# USBtoUART.net
KiCad netlist of a schematic drawn in Altium Designer
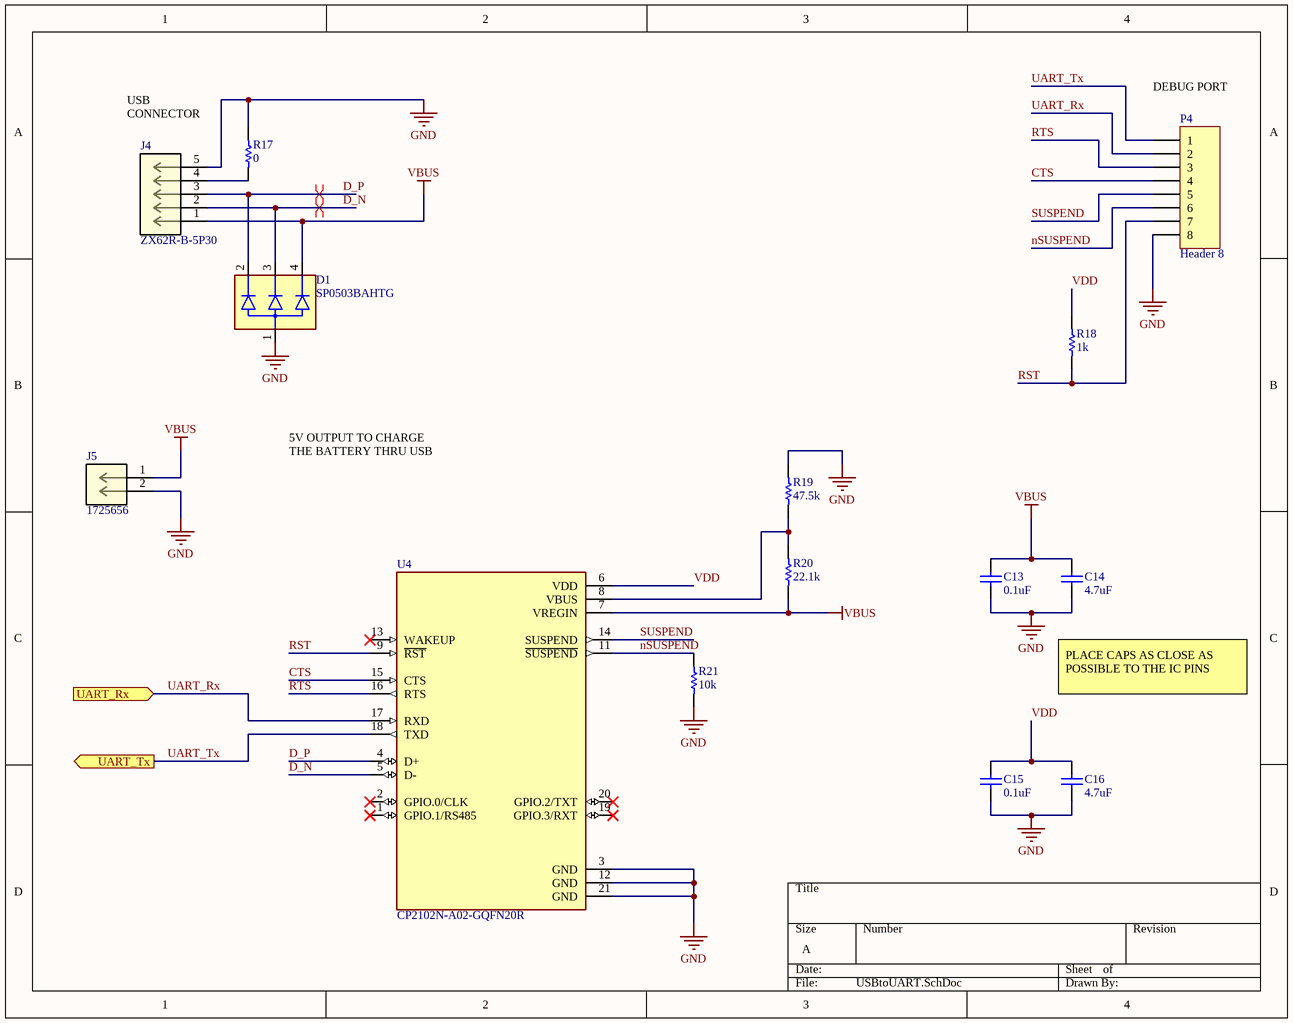
[diagram p0: USBtoUART.SchDoc]

(export (version "E")
  (design (tool "Eeschema 10.0.6"))
  (components
    (comp (ref "C13")
      (value "0.1uF")
      (footprint "0402cap")
      (description "0402 Ceramic Chip Capacitor - Standard")
      (fields (field (name "Comment") "C0402"))
      (libsource (lib "Standard Components") (part "C0402"))
    )
    (comp (ref "C14")
      (value "4.7uF")
      (footprint "0805CAP")
      (description "0805 Ceramic Chip Capacitor - Standard")
      (fields (field (name "Comment") "C0805"))
      (libsource (lib "Standard Components") (part "C0805"))
    )
    (comp (ref "C15")
      (value "0.1uF")
      (footprint "0402cap")
      (description "0402 Ceramic Chip Capacitor - Standard")
      (fields (field (name "Comment") "C0402"))
      (libsource (lib "Standard Components") (part "C0402"))
    )
    (comp (ref "C16")
      (value "4.7uF")
      (footprint "0805CAP")
      (description "0805 Ceramic Chip Capacitor - Standard")
      (fields (field (name "Comment") "C0805"))
      (libsource (lib "Standard Components") (part "C0805"))
    )
    (comp (ref "D1")
      (value "SP0503BAHTG")
      (footprint "SOT143")
      (fields (field (name "MF") "{'manufacturer': u'Littelfuse Inc.'}"))
      (libsource (lib "SP0503BAHTG_Zenner diodes") (part "SP0503BAHTG"))
    )
    (comp (ref "J4")
      (value "ZX62R-B-5P30")
      (footprint "CONN_ZX62R-B-5P30_HIR")
      (description "No Description Available")
      (libsource (lib "MicroUSBReceptacle") (part "ZX62R-B-5P30"))
    )
    (comp (ref "J5")
      (value "1725656")
      (footprint "CONN_1725656_PXC")
      (description "No Description Available")
      (libsource (lib "ScrewTerminal2Position") (part "1725656"))
    )
    (comp (ref "P4")
      (value "Header 8")
      (footprint "HDR1X8")
      (description "Header, 8-Pin")
      (fields (field (name "PUBLISHER") "Altium Limited"))
      (libsource (lib "Miscellaneous Connectors") (part "Header 8"))
    )
    (comp (ref "R17")
      (value "0")
      (footprint "0805RES")
      (description "0805 Chip Resistor - Standard")
      (fields (field (name "Comment") "R0805"))
      (libsource (lib "Standard Components") (part "R0805"))
    )
    (comp (ref "R18")
      (value "1k")
      (footprint "0402RES")
      (description "0402 Chip Resistor - Standard")
      (fields (field (name "Comment") "R0402"))
      (libsource (lib "Standard Components") (part "R0402"))
    )
    (comp (ref "R19")
      (value "47.5k")
      (footprint "0805RES")
      (description "0805 Chip Resistor - Standard")
      (fields (field (name "Comment") "R0805"))
      (libsource (lib "Standard Components") (part "R0805"))
    )
    (comp (ref "R20")
      (value "22.1k")
      (footprint "0805RES")
      (description "0805 Chip Resistor - Standard")
      (fields (field (name "Comment") "R0805"))
      (libsource (lib "Standard Components") (part "R0805"))
    )
    (comp (ref "R21")
      (value "10k")
      (footprint "0402RES")
      (description "0402 Chip Resistor - Standard")
      (fields (field (name "Comment") "R0402"))
      (libsource (lib "Standard Components") (part "R0402"))
    )
    (comp (ref "U4")
      (value "CP2102N-A02-GQFN20R")
      (footprint "SILABS_CP2102N-A02-GQFN20R")
      (description "USB Bridge, USB to UART USB 2.0 UART Interface 20-QFN (3x3)")
      (fields (field (name "MF") "Silicon Labs"))
      (libsource (lib "CP2102") (part "CP2102N-A02-GQFN20R"))
    )
  )
  (nets
    (net (code "1") (name "/CTS") (class "Default")
      (node (ref "P4") (pin "4") (pinfunction "4_4") (pintype "passive"))
      (node (ref "U4") (pin "15") (pinfunction "CTS_15") (pintype "input"))
    )
    (net (code "2") (name "/D_N") (class "Default")
      (node (ref "D1") (pin "3") (pinfunction "3_3") (pintype "passive"))
      (node (ref "J4") (pin "2") (pinfunction "2_2") (pintype "passive"))
      (node (ref "U4") (pin "5") (pinfunction "D-_5") (pintype "bidirectional"))
    )
    (net (code "3") (name "/D_P") (class "Default")
      (node (ref "D1") (pin "2") (pinfunction "2_2") (pintype "passive"))
      (node (ref "J4") (pin "3") (pinfunction "3_3") (pintype "passive"))
      (node (ref "U4") (pin "4") (pinfunction "D+_4") (pintype "bidirectional"))
    )
    (net (code "4") (name "/RST") (class "Default")
      (node (ref "P4") (pin "7") (pinfunction "7_7") (pintype "passive"))
      (node (ref "R18") (pin "1") (pinfunction "1_1") (pintype "passive"))
      (node (ref "U4") (pin "9") (pinfunction "~{RST}_9") (pintype "input"))
    )
    (net (code "5") (name "/RTS") (class "Default")
      (node (ref "P4") (pin "3") (pinfunction "3_3") (pintype "passive"))
      (node (ref "U4") (pin "16") (pinfunction "RTS_16") (pintype "output"))
    )
    (net (code "6") (name "/SUSPEND") (class "Default")
      (node (ref "P4") (pin "5") (pinfunction "5_5") (pintype "passive"))
      (node (ref "U4") (pin "14") (pinfunction "SUSPEND_14") (pintype "output"))
    )
    (net (code "7") (name "/UART_Rx") (class "Default")
      (node (ref "P4") (pin "2") (pinfunction "2_2") (pintype "passive"))
      (node (ref "U4") (pin "17") (pinfunction "RXD_17") (pintype "input"))
    )
    (net (code "8") (name "/UART_Tx") (class "Default")
      (node (ref "P4") (pin "1") (pinfunction "1_1") (pintype "passive"))
      (node (ref "U4") (pin "18") (pinfunction "TXD_18") (pintype "output"))
    )
    (net (code "9") (name "/VDD") (class "Default")
      (node (ref "C15") (pin "2") (pinfunction "2_2") (pintype "passive"))
      (node (ref "C16") (pin "2") (pinfunction "2_2") (pintype "passive"))
      (node (ref "R18") (pin "2") (pinfunction "2_2") (pintype "passive"))
      (node (ref "U4") (pin "6") (pinfunction "VDD_6") (pintype "power_in"))
    )
    (net (code "10") (name "/nSUSPEND") (class "Default")
      (node (ref "P4") (pin "6") (pinfunction "6_6") (pintype "passive"))
      (node (ref "R21") (pin "2") (pinfunction "2_2") (pintype "passive"))
      (node (ref "U4") (pin "11") (pinfunction "~{SUSPEND}_11") (pintype "output"))
    )
    (net (code "11") (name "GND") (class "Default")
      (node (ref "C13") (pin "1") (pinfunction "1_1") (pintype "passive"))
      (node (ref "C14") (pin "1") (pinfunction "1_1") (pintype "passive"))
      (node (ref "C15") (pin "1") (pinfunction "1_1") (pintype "passive"))
      (node (ref "C16") (pin "1") (pinfunction "1_1") (pintype "passive"))
      (node (ref "D1") (pin "1") (pinfunction "1_1") (pintype "passive"))
      (node (ref "J4") (pin "5") (pinfunction "5_5") (pintype "passive"))
      (node (ref "J5") (pin "2") (pinfunction "2_2") (pintype "passive"))
      (node (ref "P4") (pin "8") (pinfunction "8_8") (pintype "passive"))
      (node (ref "R17") (pin "2") (pinfunction "2_2") (pintype "passive"))
      (node (ref "R19") (pin "2") (pinfunction "2_2") (pintype "passive"))
      (node (ref "R21") (pin "1") (pinfunction "1_1") (pintype "passive"))
      (node (ref "U4") (pin "12") (pinfunction "GND_12") (pintype "power_in"))
      (node (ref "U4") (pin "21") (pinfunction "GND_21") (pintype "power_in"))
      (node (ref "U4") (pin "3") (pinfunction "GND_3") (pintype "power_in"))
    )
    (net (code "12") (name "Net-(J4-Pad4)") (class "Default")
      (node (ref "J4") (pin "4") (pinfunction "4_4") (pintype "passive"))
      (node (ref "R17") (pin "1") (pinfunction "1_1") (pintype "passive"))
    )
    (net (code "13") (name "Net-(U4-VBUS)") (class "Default")
      (node (ref "R19") (pin "1") (pinfunction "1_1") (pintype "passive"))
      (node (ref "R20") (pin "2") (pinfunction "2_2") (pintype "passive"))
      (node (ref "U4") (pin "8") (pinfunction "VBUS_8") (pintype "power_in"))
    )
    (net (code "14") (name "VBUS") (class "Default")
      (node (ref "C13") (pin "2") (pinfunction "2_2") (pintype "passive"))
      (node (ref "C14") (pin "2") (pinfunction "2_2") (pintype "passive"))
      (node (ref "D1") (pin "4") (pinfunction "4_4") (pintype "passive"))
      (node (ref "J4") (pin "1") (pinfunction "1_1") (pintype "passive"))
      (node (ref "J5") (pin "1") (pinfunction "1_1") (pintype "passive"))
      (node (ref "R20") (pin "1") (pinfunction "1_1") (pintype "passive"))
      (node (ref "U4") (pin "7") (pinfunction "VREGIN_7") (pintype "power_in"))
    )
    (net (code "15") (name "unconnected-(U4-GPIO.0{slash}CLK-Pad2)") (class "Default")
      (node (ref "U4") (pin "2") (pinfunction "GPIO.0/CLK_2") (pintype "bidirectional+no_connect"))
    )
    (net (code "16") (name "unconnected-(U4-GPIO.1{slash}RS485-Pad1)") (class "Default")
      (node (ref "U4") (pin "1") (pinfunction "GPIO.1/RS485_1") (pintype "bidirectional+no_connect"))
    )
    (net (code "17") (name "unconnected-(U4-GPIO.2{slash}TXT-Pad20)") (class "Default")
      (node (ref "U4") (pin "20") (pinfunction "GPIO.2/TXT_20") (pintype "bidirectional+no_connect"))
    )
    (net (code "18") (name "unconnected-(U4-GPIO.3{slash}RXT-Pad19)") (class "Default")
      (node (ref "U4") (pin "19") (pinfunction "GPIO.3/RXT_19") (pintype "bidirectional+no_connect"))
    )
    (net (code "19") (name "unconnected-(U4-WAKEUP-Pad13)") (class "Default")
      (node (ref "U4") (pin "13") (pinfunction "WAKEUP_13") (pintype "input+no_connect"))
    )
  )
)
